# 15-M2_GNSS.net
KiCad netlist of a schematic drawn in Altium Designer
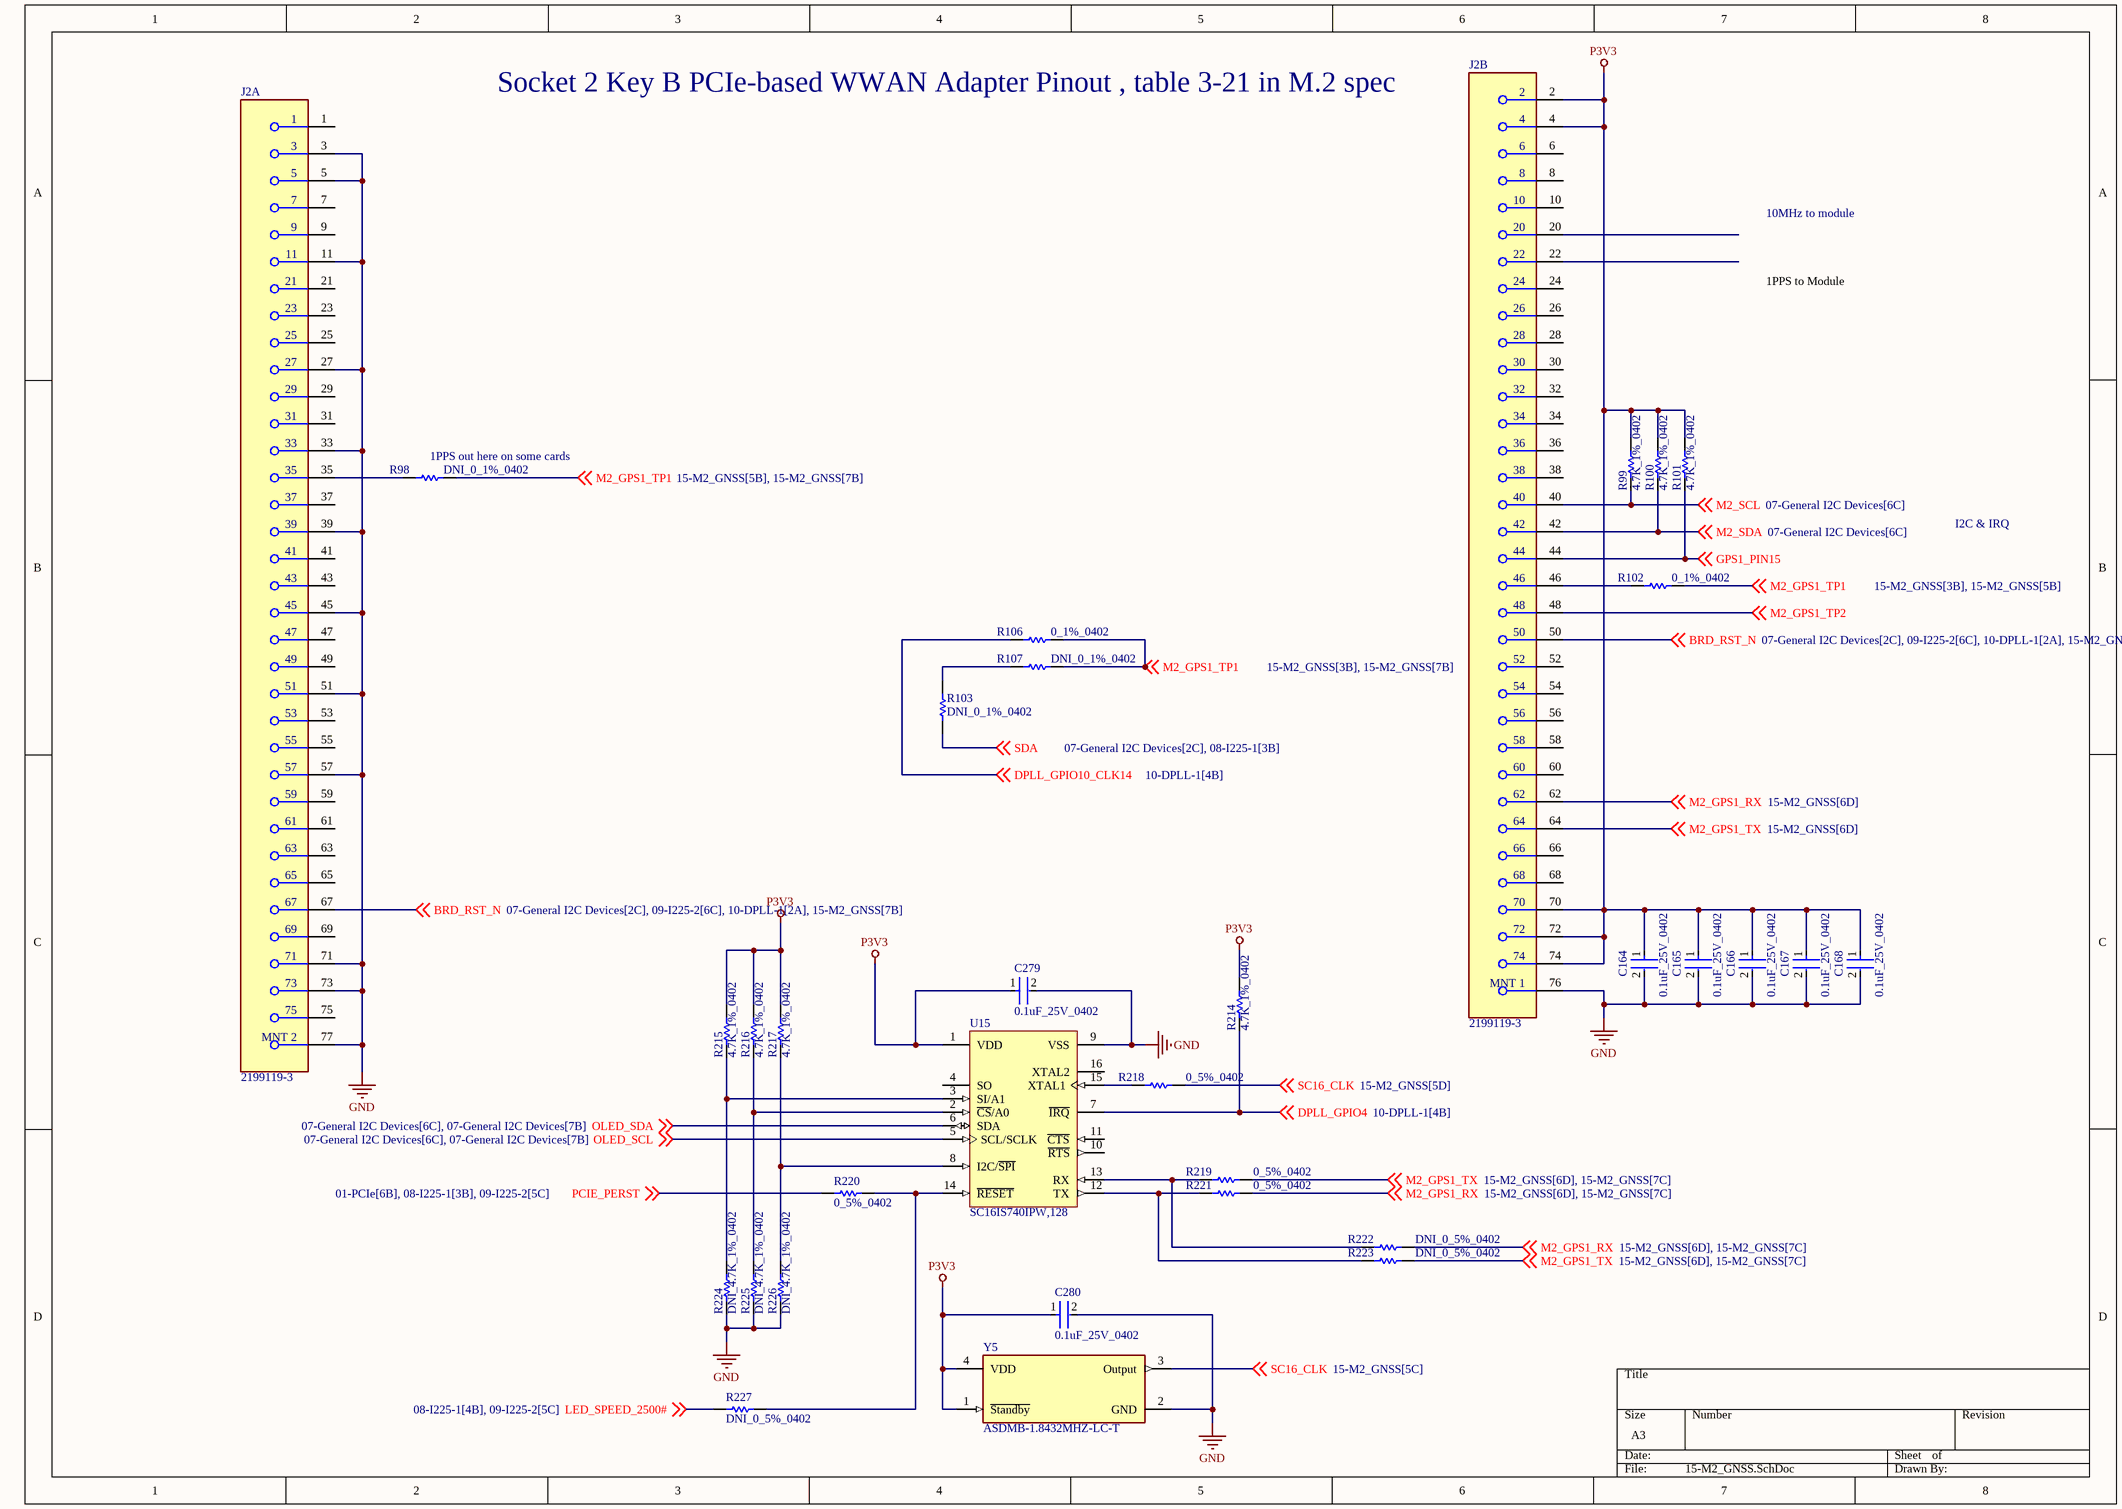
[diagram p0: 15-M2_GNSS.SchDoc]

(export (version "E")
  (design (tool "Eeschema 10.0.6"))
  (components
    (comp (ref "C164")
      (value "0.1uF_25V_0402")
      (footprint "FP-0402-L_1_0_1-W_0_5_0_1-IPC_C")
      (description "General Purpose Ceramic Capacitor, 0402, 100nF, 10%, X7R, 15%, 25V")
      (fields (field (name "VOLTAGE") "25V") (field (name "TOLERANCE") "10%"))
      (libsource (lib "Altium Content Vault") (part "b4654b650e69147ec39a6b967a45e02"))
    )
    (comp (ref "C165")
      (value "0.1uF_25V_0402")
      (footprint "FP-0402-L_1_0_1-W_0_5_0_1-IPC_C")
      (description "General Purpose Ceramic Capacitor, 0402, 100nF, 10%, X7R, 15%, 25V")
      (fields (field (name "VOLTAGE") "25V") (field (name "TOLERANCE") "10%"))
      (libsource (lib "Altium Content Vault") (part "b4654b650e69147ec39a6b967a45e02"))
    )
    (comp (ref "C166")
      (value "0.1uF_25V_0402")
      (footprint "FP-0402-L_1_0_1-W_0_5_0_1-IPC_C")
      (description "General Purpose Ceramic Capacitor, 0402, 100nF, 10%, X7R, 15%, 25V")
      (fields (field (name "VOLTAGE") "25V") (field (name "TOLERANCE") "10%"))
      (libsource (lib "Altium Content Vault") (part "b4654b650e69147ec39a6b967a45e02"))
    )
    (comp (ref "C167")
      (value "0.1uF_25V_0402")
      (footprint "FP-0402-L_1_0_1-W_0_5_0_1-IPC_C")
      (description "General Purpose Ceramic Capacitor, 0402, 100nF, 10%, X7R, 15%, 25V")
      (fields (field (name "VOLTAGE") "25V") (field (name "TOLERANCE") "10%"))
      (libsource (lib "Altium Content Vault") (part "b4654b650e69147ec39a6b967a45e02"))
    )
    (comp (ref "C168")
      (value "0.1uF_25V_0402")
      (footprint "FP-0402-L_1_0_1-W_0_5_0_1-IPC_C")
      (description "General Purpose Ceramic Capacitor, 0402, 100nF, 10%, X7R, 15%, 25V")
      (fields (field (name "VOLTAGE") "25V") (field (name "TOLERANCE") "10%"))
      (libsource (lib "Altium Content Vault") (part "b4654b650e69147ec39a6b967a45e02"))
    )
    (comp (ref "C279")
      (value "0.1uF_25V_0402")
      (footprint "FP-0402-L_1_0_1-W_0_5_0_1-IPC_C")
      (description "General Purpose Ceramic Capacitor, 0402, 100nF, 10%, X7R, 15%, 25V")
      (fields (field (name "VOLTAGE") "25V") (field (name "TOLERANCE") "10%"))
      (libsource (lib "Altium Content Vault") (part "b4654b650e69147ec39a6b967a45e02"))
    )
    (comp (ref "C280")
      (value "0.1uF_25V_0402")
      (footprint "FP-0402-L_1_0_1-W_0_5_0_1-IPC_C")
      (description "General Purpose Ceramic Capacitor, 0402, 100nF, 10%, X7R, 15%, 25V")
      (fields (field (name "VOLTAGE") "25V") (field (name "TOLERANCE") "10%"))
      (libsource (lib "Altium Content Vault") (part "b4654b650e69147ec39a6b967a45e02"))
    )
    (comp (ref "J2")
      (value "2199119-3")
      (footprint "FP-2199119-3-MFG")
      (description "CONN M.2 FEMALE 67POS 0.020 GOLD")
      (libsource (lib "Altium Content Vault") (part "a14843ccfa78e5d0b739856168502fb"))
    )
    (comp (ref "R98")
      (value "DNI_0_1%_0402")
      (footprint "RESC1005X40X25LL05T05")
      (description "Chip Resistor, 0 Ohm, 0.1 W, -55 to 155 degC, 0402 (1005 Metric), RoHS, Tape and Reel")
      (fields (field (name "MANUFACTURER") "Panasonic") (field (name "TOLERANCE") "5%"))
      (libsource (lib "Altium Content Vault") (part "RES-2"))
    )
    (comp (ref "R99")
      (value "4.7K_1%_0402")
      (footprint "RESC1005X40X25NL10T10")
      (fields (field (name "MANUFACTURER") "Bourns") (field (name "PART NUMBER") "CR0402-FX-4701GLF"))
      (libsource (lib "Altium Content Vault") (part "RES"))
    )
    (comp (ref "R100")
      (value "4.7K_1%_0402")
      (footprint "RESC1005X40X25NL10T10")
      (fields (field (name "MANUFACTURER") "Bourns") (field (name "PART NUMBER") "CR0402-FX-4701GLF"))
      (libsource (lib "Altium Content Vault") (part "RES"))
    )
    (comp (ref "R101")
      (value "4.7K_1%_0402")
      (footprint "RESC1005X40X25NL10T10")
      (fields (field (name "MANUFACTURER") "Bourns") (field (name "PART NUMBER") "CR0402-FX-4701GLF"))
      (libsource (lib "Altium Content Vault") (part "RES"))
    )
    (comp (ref "R102")
      (value "0_1%_0402")
      (footprint "RESC1005X40X25LL05T05")
      (description "Chip Resistor, 0 Ohm, 0.1 W, -55 to 155 degC, 0402 (1005 Metric), RoHS, Tape and Reel")
      (fields (field (name "MANUFACTURER") "Panasonic") (field (name "TOLERANCE") "5%"))
      (libsource (lib "Altium Content Vault") (part "RES-2"))
    )
    (comp (ref "R103")
      (value "DNI_0_1%_0402")
      (footprint "RESC1005X40X25LL05T05")
      (description "Chip Resistor, 0 Ohm, 0.1 W, -55 to 155 degC, 0402 (1005 Metric), RoHS, Tape and Reel")
      (fields (field (name "MANUFACTURER") "Panasonic") (field (name "TOLERANCE") "5%"))
      (libsource (lib "Altium Content Vault") (part "RES-2"))
    )
    (comp (ref "R106")
      (value "0_1%_0402")
      (footprint "RESC1005X40X25LL05T05")
      (description "Chip Resistor, 0 Ohm, 0.1 W, -55 to 155 degC, 0402 (1005 Metric), RoHS, Tape and Reel")
      (fields (field (name "MANUFACTURER") "Panasonic") (field (name "TOLERANCE") "5%"))
      (libsource (lib "Altium Content Vault") (part "RES-2"))
    )
    (comp (ref "R107")
      (value "DNI_0_1%_0402")
      (footprint "RESC1005X40X25LL05T05")
      (description "Chip Resistor, 0 Ohm, 0.1 W, -55 to 155 degC, 0402 (1005 Metric), RoHS, Tape and Reel")
      (fields (field (name "MANUFACTURER") "Panasonic") (field (name "TOLERANCE") "5%"))
      (libsource (lib "Altium Content Vault") (part "RES-2"))
    )
    (comp (ref "R214")
      (value "4.7K_1%_0402")
      (footprint "RESC1005X40X25NL10T10")
      (fields (field (name "MANUFACTURER") "Bourns") (field (name "PART NUMBER") "CR0402-FX-4701GLF"))
      (libsource (lib "Altium Content Vault") (part "RES"))
    )
    (comp (ref "R215")
      (value "4.7K_1%_0402")
      (footprint "RESC1005X40X25NL10T10")
      (fields (field (name "MANUFACTURER") "Bourns") (field (name "PART NUMBER") "CR0402-FX-4701GLF"))
      (libsource (lib "Altium Content Vault") (part "RES"))
    )
    (comp (ref "R216")
      (value "4.7K_1%_0402")
      (footprint "RESC1005X40X25NL10T10")
      (fields (field (name "MANUFACTURER") "Bourns") (field (name "PART NUMBER") "CR0402-FX-4701GLF"))
      (libsource (lib "Altium Content Vault") (part "RES"))
    )
    (comp (ref "R217")
      (value "4.7K_1%_0402")
      (footprint "RESC1005X40X25NL10T10")
      (fields (field (name "MANUFACTURER") "Bourns") (field (name "PART NUMBER") "CR0402-FX-4701GLF"))
      (libsource (lib "Altium Content Vault") (part "RES"))
    )
    (comp (ref "R218")
      (value "0_5%_0402")
      (footprint "RESC1005X40X25LL10T10")
      (fields (field (name "MANUFACTURER") "KOA Speer") (field (name "PART NUMBER") "RK73Z1ETTP"))
      (libsource (lib "Altium Content Vault") (part "RES"))
    )
    (comp (ref "R219")
      (value "0_5%_0402")
      (footprint "RESC1005X40X25LL10T10")
      (fields (field (name "MANUFACTURER") "KOA Speer") (field (name "PART NUMBER") "RK73Z1ETTP"))
      (libsource (lib "Altium Content Vault") (part "RES"))
    )
    (comp (ref "R220")
      (value "0_5%_0402")
      (footprint "RESC1005X40X25LL10T10")
      (fields (field (name "MANUFACTURER") "KOA Speer") (field (name "PART NUMBER") "RK73Z1ETTP"))
      (libsource (lib "Altium Content Vault") (part "RES"))
    )
    (comp (ref "R221")
      (value "0_5%_0402")
      (footprint "RESC1005X40X25LL10T10")
      (fields (field (name "MANUFACTURER") "KOA Speer") (field (name "PART NUMBER") "RK73Z1ETTP"))
      (libsource (lib "Altium Content Vault") (part "RES"))
    )
    (comp (ref "R222")
      (value "DNI_0_5%_0402")
      (footprint "RESC1005X40X25LL10T10")
      (fields (field (name "MANUFACTURER") "KOA Speer") (field (name "PART NUMBER") "RK73Z1ETTP"))
      (libsource (lib "Altium Content Vault") (part "RES"))
    )
    (comp (ref "R223")
      (value "DNI_0_5%_0402")
      (footprint "RESC1005X40X25LL10T10")
      (fields (field (name "MANUFACTURER") "KOA Speer") (field (name "PART NUMBER") "RK73Z1ETTP"))
      (libsource (lib "Altium Content Vault") (part "RES"))
    )
    (comp (ref "R224")
      (value "DNI_4.7K_1%_0402")
      (footprint "RESC1005X40X25NL10T10")
      (fields (field (name "MANUFACTURER") "Bourns") (field (name "PART NUMBER") "CR0402-FX-4701GLF"))
      (libsource (lib "Altium Content Vault") (part "RES"))
    )
    (comp (ref "R225")
      (value "DNI_4.7K_1%_0402")
      (footprint "RESC1005X40X25NL10T10")
      (fields (field (name "MANUFACTURER") "Bourns") (field (name "PART NUMBER") "CR0402-FX-4701GLF"))
      (libsource (lib "Altium Content Vault") (part "RES"))
    )
    (comp (ref "R226")
      (value "DNI_4.7K_1%_0402")
      (footprint "RESC1005X40X25NL10T10")
      (fields (field (name "MANUFACTURER") "Bourns") (field (name "PART NUMBER") "CR0402-FX-4701GLF"))
      (libsource (lib "Altium Content Vault") (part "RES"))
    )
    (comp (ref "R227")
      (value "DNI_0_5%_0402")
      (footprint "RESC1005X40X25LL10T10")
      (fields (field (name "MANUFACTURER") "KOA Speer") (field (name "PART NUMBER") "RK73Z1ETTP"))
      (libsource (lib "Altium Content Vault") (part "RES"))
    )
    (comp (ref "U15")
      (value "SC16IS740IPW,128")
      (footprint "NXP-SOT403-1_V")
      (fields (field (name "GENERIC PART NUMBER") "SC16IS740"))
      (libsource (lib "Altium Content Vault") (part "NXP-SC16IS740-SOT403-1-16"))
    )
    (comp (ref "Y5")
      (value "ASDMB-1.8432MHZ-LC-T")
      (footprint "FP-ASDM-ASDMB-MFG")
      (description "MEMS Oscillator 1.8432MHz ±50ppm LVCMOS 1.8V~3.3V SMD 2.5x2mm")
      (libsource (lib "Altium Content Vault") (part "d1c68ac5f38726358044f3b7e06346c"))
    )
  )
  (nets
    (net (code "1") (name "BRD_RST_N") (class "Default")
      (node (ref "J2") (pin "50") (pinfunction "50_50") (pintype "passive"))
      (node (ref "J2") (pin "67") (pinfunction "67_67") (pintype "passive"))
    )
    (net (code "2") (name "DPLL_GPIO4") (class "Default")
      (node (ref "R214") (pin "1") (pinfunction "1_1") (pintype "passive"))
      (node (ref "U15") (pin "7") (pinfunction "~{IRQ}_7") (pintype "open_collector"))
    )
    (net (code "3") (name "DPLL_GPIO10_CLK14") (class "Default")
      (node (ref "R106") (pin "1") (pinfunction "1_1") (pintype "passive"))
    )
    (net (code "4") (name "GND") (class "Default")
      (node (ref "C164") (pin "2") (pinfunction "2_2") (pintype "passive"))
      (node (ref "C165") (pin "2") (pinfunction "2_2") (pintype "passive"))
      (node (ref "C166") (pin "2") (pinfunction "2_2") (pintype "passive"))
      (node (ref "C167") (pin "2") (pinfunction "2_2") (pintype "passive"))
      (node (ref "C168") (pin "2") (pinfunction "2_2") (pintype "passive"))
      (node (ref "C279") (pin "2") (pinfunction "2_2") (pintype "passive"))
      (node (ref "C280") (pin "2") (pinfunction "2_2") (pintype "passive"))
      (node (ref "J2") (pin "11") (pinfunction "11_11") (pintype "passive"))
      (node (ref "J2") (pin "27") (pinfunction "27_27") (pintype "passive"))
      (node (ref "J2") (pin "3") (pinfunction "3_3") (pintype "passive"))
      (node (ref "J2") (pin "33") (pinfunction "33_33") (pintype "passive"))
      (node (ref "J2") (pin "39") (pinfunction "39_39") (pintype "passive"))
      (node (ref "J2") (pin "45") (pinfunction "45_45") (pintype "passive"))
      (node (ref "J2") (pin "5") (pinfunction "5_5") (pintype "passive"))
      (node (ref "J2") (pin "51") (pinfunction "51_51") (pintype "passive"))
      (node (ref "J2") (pin "57") (pinfunction "57_57") (pintype "passive"))
      (node (ref "J2") (pin "71") (pinfunction "71_71") (pintype "passive"))
      (node (ref "J2") (pin "73") (pinfunction "73_73") (pintype "passive"))
      (node (ref "J2") (pin "76") (pinfunction "MNT_1_76") (pintype "passive"))
      (node (ref "J2") (pin "77") (pinfunction "MNT_2_77") (pintype "passive"))
      (node (ref "R224") (pin "1") (pinfunction "1_1") (pintype "passive"))
      (node (ref "R225") (pin "1") (pinfunction "1_1") (pintype "passive"))
      (node (ref "R226") (pin "1") (pinfunction "1_1") (pintype "passive"))
      (node (ref "U15") (pin "9") (pinfunction "VSS_9") (pintype "power_in"))
      (node (ref "Y5") (pin "2") (pinfunction "GND_2") (pintype "power_in"))
    )
    (net (code "5") (name "GPS1_PIN15") (class "Default")
      (node (ref "J2") (pin "44") (pinfunction "44_44") (pintype "passive"))
      (node (ref "R101") (pin "1") (pinfunction "1_1") (pintype "passive"))
    )
    (net (code "6") (name "LED_SPEED_2500#") (class "Default")
      (node (ref "R227") (pin "2") (pinfunction "2_2") (pintype "passive"))
    )
    (net (code "7") (name "M2_GPS1_RX") (class "Default")
      (node (ref "J2") (pin "62") (pinfunction "62_62") (pintype "passive"))
      (node (ref "R221") (pin "1") (pinfunction "1_1") (pintype "passive"))
      (node (ref "R222") (pin "1") (pinfunction "1_1") (pintype "passive"))
    )
    (net (code "8") (name "M2_GPS1_TP1") (class "Default")
      (node (ref "R102") (pin "2") (pinfunction "2_2") (pintype "passive"))
      (node (ref "R106") (pin "2") (pinfunction "2_2") (pintype "passive"))
      (node (ref "R107") (pin "2") (pinfunction "2_2") (pintype "passive"))
      (node (ref "R98") (pin "2") (pinfunction "2_2") (pintype "passive"))
    )
    (net (code "9") (name "M2_GPS1_TP2") (class "Default")
      (node (ref "J2") (pin "48") (pinfunction "48_48") (pintype "passive"))
    )
    (net (code "10") (name "M2_GPS1_TX") (class "Default")
      (node (ref "J2") (pin "64") (pinfunction "64_64") (pintype "passive"))
      (node (ref "R219") (pin "1") (pinfunction "1_1") (pintype "passive"))
      (node (ref "R223") (pin "1") (pinfunction "1_1") (pintype "passive"))
    )
    (net (code "11") (name "M2_SCL") (class "Default")
      (node (ref "J2") (pin "40") (pinfunction "40_40") (pintype "passive"))
      (node (ref "R99") (pin "1") (pinfunction "1_1") (pintype "passive"))
    )
    (net (code "12") (name "M2_SDA") (class "Default")
      (node (ref "J2") (pin "42") (pinfunction "42_42") (pintype "passive"))
      (node (ref "R100") (pin "1") (pinfunction "1_1") (pintype "passive"))
    )
    (net (code "13") (name "Net-(J2-Pad35)") (class "Default")
      (node (ref "J2") (pin "35") (pinfunction "35_35") (pintype "passive"))
      (node (ref "R98") (pin "1") (pinfunction "1_1") (pintype "passive"))
    )
    (net (code "14") (name "Net-(J2-Pad46)") (class "Default")
      (node (ref "J2") (pin "46") (pinfunction "46_46") (pintype "passive"))
      (node (ref "R102") (pin "1") (pinfunction "1_1") (pintype "passive"))
    )
    (net (code "15") (name "Net-(R103-Pad2)") (class "Default")
      (node (ref "R103") (pin "2") (pinfunction "2_2") (pintype "passive"))
      (node (ref "R107") (pin "1") (pinfunction "1_1") (pintype "passive"))
    )
    (net (code "16") (name "Net-(U15-I2C{slash}~{SPI})") (class "Default")
      (node (ref "R217") (pin "1") (pinfunction "1_1") (pintype "passive"))
      (node (ref "R226") (pin "2") (pinfunction "2_2") (pintype "passive"))
      (node (ref "U15") (pin "8") (pinfunction "I2C/~{SPI}_8") (pintype "input"))
    )
    (net (code "17") (name "Net-(U15-RX)") (class "Default")
      (node (ref "R219") (pin "2") (pinfunction "2_2") (pintype "passive"))
      (node (ref "R222") (pin "2") (pinfunction "2_2") (pintype "passive"))
      (node (ref "U15") (pin "13") (pinfunction "RX_13") (pintype "input"))
    )
    (net (code "18") (name "Net-(U15-SI{slash}A1)") (class "Default")
      (node (ref "R215") (pin "1") (pinfunction "1_1") (pintype "passive"))
      (node (ref "R224") (pin "2") (pinfunction "2_2") (pintype "passive"))
      (node (ref "U15") (pin "3") (pinfunction "SI/A1_3") (pintype "input"))
    )
    (net (code "19") (name "Net-(U15-TX)") (class "Default")
      (node (ref "R221") (pin "2") (pinfunction "2_2") (pintype "passive"))
      (node (ref "R223") (pin "2") (pinfunction "2_2") (pintype "passive"))
      (node (ref "U15") (pin "12") (pinfunction "TX_12") (pintype "output"))
    )
    (net (code "20") (name "Net-(U15-XTAL1)") (class "Default")
      (node (ref "R218") (pin "2") (pinfunction "2_2") (pintype "passive"))
      (node (ref "U15") (pin "15") (pinfunction "XTAL1_15") (pintype "input"))
    )
    (net (code "21") (name "Net-(U15-~{CS}{slash}A0)") (class "Default")
      (node (ref "R216") (pin "1") (pinfunction "1_1") (pintype "passive"))
      (node (ref "R225") (pin "2") (pinfunction "2_2") (pintype "passive"))
      (node (ref "U15") (pin "2") (pinfunction "~{CS}/A0_2") (pintype "input"))
    )
    (net (code "22") (name "Net-(U15-~{RESET})") (class "Default")
      (node (ref "R220") (pin "1") (pinfunction "1_1") (pintype "passive"))
      (node (ref "R227") (pin "1") (pinfunction "1_1") (pintype "passive"))
      (node (ref "U15") (pin "14") (pinfunction "~{RESET}_14") (pintype "input"))
    )
    (net (code "23") (name "OLED_SCL") (class "Default")
      (node (ref "U15") (pin "5") (pinfunction "SCL/SCLK_5") (pintype "input"))
    )
    (net (code "24") (name "OLED_SDA") (class "Default")
      (node (ref "U15") (pin "6") (pinfunction "SDA_6") (pintype "bidirectional"))
    )
    (net (code "25") (name "P3V3") (class "Default")
      (node (ref "C164") (pin "1") (pinfunction "1_1") (pintype "passive"))
      (node (ref "C165") (pin "1") (pinfunction "1_1") (pintype "passive"))
      (node (ref "C166") (pin "1") (pinfunction "1_1") (pintype "passive"))
      (node (ref "C167") (pin "1") (pinfunction "1_1") (pintype "passive"))
      (node (ref "C168") (pin "1") (pinfunction "1_1") (pintype "passive"))
      (node (ref "C279") (pin "1") (pinfunction "1_1") (pintype "passive"))
      (node (ref "C280") (pin "1") (pinfunction "1_1") (pintype "passive"))
      (node (ref "J2") (pin "2") (pinfunction "2_2") (pintype "passive"))
      (node (ref "J2") (pin "4") (pinfunction "4_4") (pintype "passive"))
      (node (ref "J2") (pin "70") (pinfunction "70_70") (pintype "passive"))
      (node (ref "J2") (pin "72") (pinfunction "72_72") (pintype "passive"))
      (node (ref "J2") (pin "74") (pinfunction "74_74") (pintype "passive"))
      (node (ref "R100") (pin "2") (pinfunction "2_2") (pintype "passive"))
      (node (ref "R101") (pin "2") (pinfunction "2_2") (pintype "passive"))
      (node (ref "R214") (pin "2") (pinfunction "2_2") (pintype "passive"))
      (node (ref "R215") (pin "2") (pinfunction "2_2") (pintype "passive"))
      (node (ref "R216") (pin "2") (pinfunction "2_2") (pintype "passive"))
      (node (ref "R217") (pin "2") (pinfunction "2_2") (pintype "passive"))
      (node (ref "R99") (pin "2") (pinfunction "2_2") (pintype "passive"))
      (node (ref "U15") (pin "1") (pinfunction "VDD_1") (pintype "power_in"))
      (node (ref "Y5") (pin "1") (pinfunction "~{Standby}_1") (pintype "input"))
      (node (ref "Y5") (pin "4") (pinfunction "VDD_4") (pintype "power_in"))
    )
    (net (code "26") (name "PCIE_PERST") (class "Default")
      (node (ref "R220") (pin "2") (pinfunction "2_2") (pintype "passive"))
    )
    (net (code "27") (name "SC16_CLK") (class "Default")
      (node (ref "R218") (pin "1") (pinfunction "1_1") (pintype "passive"))
      (node (ref "Y5") (pin "3") (pinfunction "Output_3") (pintype "output"))
    )
    (net (code "28") (name "SDA") (class "Default")
      (node (ref "R103") (pin "1") (pinfunction "1_1") (pintype "passive"))
    )
    (net (code "29") (name "unconnected-(J2-Pad1)") (class "Default")
      (node (ref "J2") (pin "1") (pinfunction "1_1") (pintype "passive"))
    )
    (net (code "30") (name "unconnected-(J2-Pad6)") (class "Default")
      (node (ref "J2") (pin "6") (pinfunction "6_6") (pintype "passive"))
    )
    (net (code "31") (name "unconnected-(J2-Pad7)") (class "Default")
      (node (ref "J2") (pin "7") (pinfunction "7_7") (pintype "passive"))
    )
    (net (code "32") (name "unconnected-(J2-Pad8)") (class "Default")
      (node (ref "J2") (pin "8") (pinfunction "8_8") (pintype "passive"))
    )
    (net (code "33") (name "unconnected-(J2-Pad9)") (class "Default")
      (node (ref "J2") (pin "9") (pinfunction "9_9") (pintype "passive"))
    )
    (net (code "34") (name "unconnected-(J2-Pad10)") (class "Default")
      (node (ref "J2") (pin "10") (pinfunction "10_10") (pintype "passive"))
    )
    (net (code "35") (name "unconnected-(J2-Pad20)") (class "Default")
      (node (ref "J2") (pin "20") (pinfunction "20_20") (pintype "passive"))
    )
    (net (code "36") (name "unconnected-(J2-Pad21)") (class "Default")
      (node (ref "J2") (pin "21") (pinfunction "21_21") (pintype "passive"))
    )
    (net (code "37") (name "unconnected-(J2-Pad22)") (class "Default")
      (node (ref "J2") (pin "22") (pinfunction "22_22") (pintype "passive"))
    )
    (net (code "38") (name "unconnected-(J2-Pad23)") (class "Default")
      (node (ref "J2") (pin "23") (pinfunction "23_23") (pintype "passive"))
    )
    (net (code "39") (name "unconnected-(J2-Pad24)") (class "Default")
      (node (ref "J2") (pin "24") (pinfunction "24_24") (pintype "passive"))
    )
    (net (code "40") (name "unconnected-(J2-Pad25)") (class "Default")
      (node (ref "J2") (pin "25") (pinfunction "25_25") (pintype "passive"))
    )
    (net (code "41") (name "unconnected-(J2-Pad26)") (class "Default")
      (node (ref "J2") (pin "26") (pinfunction "26_26") (pintype "passive"))
    )
    (net (code "42") (name "unconnected-(J2-Pad28)") (class "Default")
      (node (ref "J2") (pin "28") (pinfunction "28_28") (pintype "passive"))
    )
    (net (code "43") (name "unconnected-(J2-Pad29)") (class "Default")
      (node (ref "J2") (pin "29") (pinfunction "29_29") (pintype "passive"))
    )
    (net (code "44") (name "unconnected-(J2-Pad30)") (class "Default")
      (node (ref "J2") (pin "30") (pinfunction "30_30") (pintype "passive"))
    )
    (net (code "45") (name "unconnected-(J2-Pad31)") (class "Default")
      (node (ref "J2") (pin "31") (pinfunction "31_31") (pintype "passive"))
    )
    (net (code "46") (name "unconnected-(J2-Pad32)") (class "Default")
      (node (ref "J2") (pin "32") (pinfunction "32_32") (pintype "passive"))
    )
    (net (code "47") (name "unconnected-(J2-Pad34)") (class "Default")
      (node (ref "J2") (pin "34") (pinfunction "34_34") (pintype "passive"))
    )
    (net (code "48") (name "unconnected-(J2-Pad36)") (class "Default")
      (node (ref "J2") (pin "36") (pinfunction "36_36") (pintype "passive"))
    )
    (net (code "49") (name "unconnected-(J2-Pad37)") (class "Default")
      (node (ref "J2") (pin "37") (pinfunction "37_37") (pintype "passive"))
    )
    (net (code "50") (name "unconnected-(J2-Pad38)") (class "Default")
      (node (ref "J2") (pin "38") (pinfunction "38_38") (pintype "passive"))
    )
    (net (code "51") (name "unconnected-(J2-Pad41)") (class "Default")
      (node (ref "J2") (pin "41") (pinfunction "41_41") (pintype "passive"))
    )
    (net (code "52") (name "unconnected-(J2-Pad43)") (class "Default")
      (node (ref "J2") (pin "43") (pinfunction "43_43") (pintype "passive"))
    )
    (net (code "53") (name "unconnected-(J2-Pad47)") (class "Default")
      (node (ref "J2") (pin "47") (pinfunction "47_47") (pintype "passive"))
    )
    (net (code "54") (name "unconnected-(J2-Pad49)") (class "Default")
      (node (ref "J2") (pin "49") (pinfunction "49_49") (pintype "passive"))
    )
    (net (code "55") (name "unconnected-(J2-Pad52)") (class "Default")
      (node (ref "J2") (pin "52") (pinfunction "52_52") (pintype "passive"))
    )
    (net (code "56") (name "unconnected-(J2-Pad53)") (class "Default")
      (node (ref "J2") (pin "53") (pinfunction "53_53") (pintype "passive"))
    )
    (net (code "57") (name "unconnected-(J2-Pad54)") (class "Default")
      (node (ref "J2") (pin "54") (pinfunction "54_54") (pintype "passive"))
    )
    (net (code "58") (name "unconnected-(J2-Pad55)") (class "Default")
      (node (ref "J2") (pin "55") (pinfunction "55_55") (pintype "passive"))
    )
    (net (code "59") (name "unconnected-(J2-Pad56)") (class "Default")
      (node (ref "J2") (pin "56") (pinfunction "56_56") (pintype "passive"))
    )
    (net (code "60") (name "unconnected-(J2-Pad58)") (class "Default")
      (node (ref "J2") (pin "58") (pinfunction "58_58") (pintype "passive"))
    )
    (net (code "61") (name "unconnected-(J2-Pad59)") (class "Default")
      (node (ref "J2") (pin "59") (pinfunction "59_59") (pintype "passive"))
    )
    (net (code "62") (name "unconnected-(J2-Pad60)") (class "Default")
      (node (ref "J2") (pin "60") (pinfunction "60_60") (pintype "passive"))
    )
    (net (code "63") (name "unconnected-(J2-Pad61)") (class "Default")
      (node (ref "J2") (pin "61") (pinfunction "61_61") (pintype "passive"))
    )
    (net (code "64") (name "unconnected-(J2-Pad63)") (class "Default")
      (node (ref "J2") (pin "63") (pinfunction "63_63") (pintype "passive"))
    )
    (net (code "65") (name "unconnected-(J2-Pad65)") (class "Default")
      (node (ref "J2") (pin "65") (pinfunction "65_65") (pintype "passive"))
    )
    (net (code "66") (name "unconnected-(J2-Pad66)") (class "Default")
      (node (ref "J2") (pin "66") (pinfunction "66_66") (pintype "passive"))
    )
    (net (code "67") (name "unconnected-(J2-Pad68)") (class "Default")
      (node (ref "J2") (pin "68") (pinfunction "68_68") (pintype "passive"))
    )
    (net (code "68") (name "unconnected-(J2-Pad69)") (class "Default")
      (node (ref "J2") (pin "69") (pinfunction "69_69") (pintype "passive"))
    )
    (net (code "69") (name "unconnected-(J2-Pad75)") (class "Default")
      (node (ref "J2") (pin "75") (pinfunction "75_75") (pintype "passive"))
    )
    (net (code "70") (name "unconnected-(U15-SO-Pad4)") (class "Default")
      (node (ref "U15") (pin "4") (pinfunction "SO_4") (pintype "tri_state"))
    )
    (net (code "71") (name "unconnected-(U15-XTAL2-Pad16)") (class "Default")
      (node (ref "U15") (pin "16") (pinfunction "XTAL2_16") (pintype "passive"))
    )
    (net (code "72") (name "unconnected-(U15-~{CTS}-Pad11)") (class "Default")
      (node (ref "U15") (pin "11") (pinfunction "~{CTS}_11") (pintype "input"))
    )
    (net (code "73") (name "unconnected-(U15-~{RTS}-Pad10)") (class "Default")
      (node (ref "U15") (pin "10") (pinfunction "~{RTS}_10") (pintype "output"))
    )
  )
)
